# LM7805FixedReg.net
KiCad netlist of a schematic drawn in Altium Designer
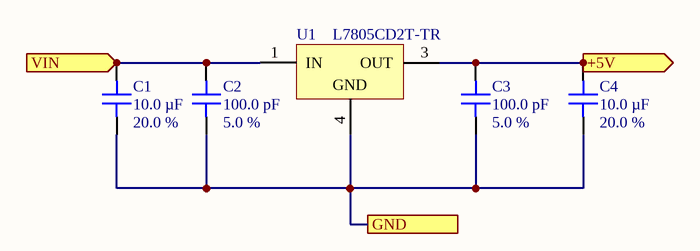
[diagram p0: LM7805FixedReg.SchDoc]

(export (version "E")
  (design (tool "Eeschema 10.0.6"))
  (components
    (comp (ref "C1")
      (value "10.0 µF")
      (footprint "PCB - CAPACITOR - MLCC - CAP 0603_1608")
      (description "10 µF ±20% 16V Ceramic Capacitor X5R 0603 (1608 Metric)")
      (fields
        (field (name "ROWAN PART NUMBER") "1572")
        (field (name "TOLERANCE") "20.0 %")
        (field (name "MANUFACTURER") "YAGEO")
      )
      (libsource (lib "RowanAltiumLibrary") (part "SCH - PASSIVES - CAPACITOR"))
    )
    (comp (ref "C2")
      (value "100.0 pF")
      (footprint "PCB - CAPACITOR - MLCC - CAP 0603_1608")
      (description "100 pF ±5% 50V Ceramic Capacitor X7R 0603 (1608 Metric)")
      (fields
        (field (name "ROWAN PART NUMBER") "1535")
        (field (name "TOLERANCE") "5.0 %")
        (field (name "MANUFACTURER") "YAGEO")
      )
      (libsource (lib "RowanAltiumLibrary") (part "SCH - PASSIVES - CAPACITOR"))
    )
    (comp (ref "C3")
      (value "100.0 pF")
      (footprint "PCB - CAPACITOR - MLCC - CAP 0603_1608")
      (description "100 pF ±5% 50V Ceramic Capacitor X7R 0603 (1608 Metric)")
      (fields
        (field (name "ROWAN PART NUMBER") "1535")
        (field (name "TOLERANCE") "5.0 %")
        (field (name "MANUFACTURER") "YAGEO")
      )
      (libsource (lib "RowanAltiumLibrary") (part "SCH - PASSIVES - CAPACITOR"))
    )
    (comp (ref "C4")
      (value "10.0 µF")
      (footprint "PCB - CAPACITOR - MLCC - CAP 0603_1608")
      (description "10 µF ±20% 16V Ceramic Capacitor X5R 0603 (1608 Metric)")
      (fields
        (field (name "ROWAN PART NUMBER") "1572")
        (field (name "TOLERANCE") "20.0 %")
        (field (name "MANUFACTURER") "YAGEO")
      )
      (libsource (lib "RowanAltiumLibrary") (part "SCH - PASSIVES - CAPACITOR"))
    )
    (comp (ref "U1")
      (value "L7805CD2T-TR")
      (footprint "TO-263_M")
      (description "Positive Voltage Regulator, 3-Pin D2PAK, Tape and Reel")
      (libsource (lib "Altium Content Vault") (part "PM-REG-L4940-SOT3"))
    )
  )
  (nets
    (net (code "1") (name "/+5V") (class "Default")
      (node (ref "C3") (pin "2") (pinfunction "2_2") (pintype "passive"))
      (node (ref "C4") (pin "2") (pinfunction "2_2") (pintype "passive"))
      (node (ref "U1") (pin "3") (pinfunction "OUT_3") (pintype "power_in"))
    )
    (net (code "2") (name "/GND") (class "Default")
      (node (ref "C1") (pin "1") (pinfunction "1_1") (pintype "passive"))
      (node (ref "C2") (pin "1") (pinfunction "1_1") (pintype "passive"))
      (node (ref "C3") (pin "1") (pinfunction "1_1") (pintype "passive"))
      (node (ref "C4") (pin "1") (pinfunction "1_1") (pintype "passive"))
      (node (ref "U1") (pin "4") (pinfunction "GND_4") (pintype "power_in"))
    )
    (net (code "3") (name "/VIN") (class "Default")
      (node (ref "C1") (pin "2") (pinfunction "2_2") (pintype "passive"))
      (node (ref "C2") (pin "2") (pinfunction "2_2") (pintype "passive"))
      (node (ref "U1") (pin "1") (pinfunction "IN_1") (pintype "power_in"))
    )
  )
)
